# Sensors.net
KiCad netlist of a schematic drawn in Altium Designer
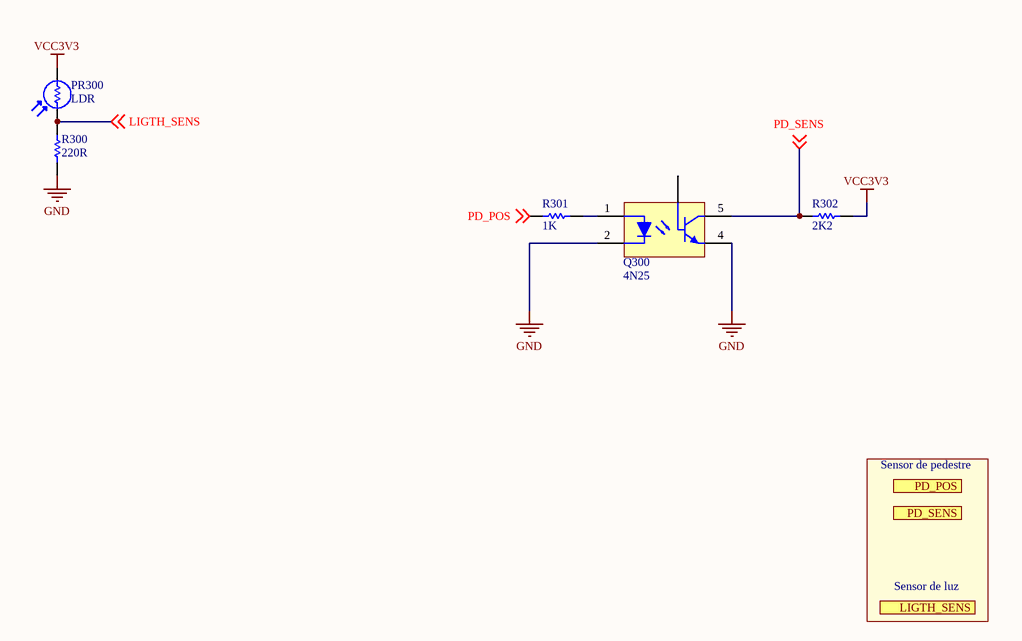
[diagram p0: Sensors.SchDoc]

(export (version "E")
  (design (tool "Eeschema 10.0.6"))
  (components
    (comp (ref "PR300")
      (value "LDR")
      (footprint "STL:LDR 3x0.5")
      (description "THROUGH HOLE PHOTORESISTORS ROHS")
      (fields
        (field (name "MANUFACTURER") "JCHL(Shenzhen Jing Chuang He Li Tech)")
        (field (name "MANUFACTURER PART NUMBER") "GL5506(4-7K)")
      )
      (libsource (lib "STL") (part "LDR GL5506(4-7K) SMD"))
    )
    (comp (ref "Q300")
      (value "4N25")
      (footprint "STL:6-SMD")
      (description "OPTOISO 4.17KV TRANS W/BASE 6SMD")
      (fields
        (field (name "MANUFACTURER") "ON Semiconductor")
        (field (name "MANUFACTURER PART NUMBER") "4N25SR2M")
      )
      (libsource (lib "STL") (part "OPTOISO 4N25S 2.5KV TRANS W/BASE 6SMD"))
    )
    (comp (ref "R300")
      (value "220R")
      (footprint "STL:CR2012-0805")
      (description "RES SMD 220 OHM 5% 1/8W 0805")
      (fields
        (field (name "MANUFACTURER") "Panasonic Electronic Components")
        (field (name "MANUFACTURER PART NUMBER") "ERJ-6GEYJ221V")
      )
      (libsource (lib "STL") (part "RES 220R OHM 5% 1/8W 0805 SMD"))
    )
    (comp (ref "R301")
      (value "1K")
      (footprint "STL:CR2012-0805")
      (description "RES SMD 1K OHM 1% 1/8W 0805")
      (fields
        (field (name "MANUFACTURER") "Yageo")
        (field (name "MANUFACTURER PART NUMBER") "RC0805FR-071KL")
      )
      (libsource (lib "STL") (part "RES 1K OHM 1% 1/8W 0805 SMD"))
    )
    (comp (ref "R302")
      (value "2K2")
      (footprint "STL:CR2012-0805")
      (description "RES SMD 2.2K OHM 5% 1/8W 0805")
      (fields
        (field (name "MANUFACTURER") "Panasonic Electronic Components")
        (field (name "PART#") "ERJ-6GEYJ222V")
      )
      (libsource (lib "STL") (part "RES 2K2 OHM 1/8W 5% 0805 SMD"))
    )
  )
  (nets
    (net (code "1") (name "GND") (class "Default")
      (node (ref "Q300") (pin "2") (pinfunction "K_2") (pintype "passive"))
      (node (ref "Q300") (pin "4") (pinfunction "E_4") (pintype "passive"))
      (node (ref "R300") (pin "1") (pinfunction "1_1") (pintype "passive"))
    )
    (net (code "2") (name "LIGTH_SENS") (class "Default")
      (node (ref "PR300") (pin "1") (pinfunction "1_1") (pintype "passive"))
      (node (ref "R300") (pin "2") (pinfunction "2_2") (pintype "passive"))
    )
    (net (code "3") (name "Net-(Q300-A)") (class "Default")
      (node (ref "Q300") (pin "1") (pinfunction "A_1") (pintype "passive"))
      (node (ref "R301") (pin "2") (pinfunction "2_2") (pintype "passive"))
    )
    (net (code "4") (name "PD_POS") (class "Default")
      (node (ref "R301") (pin "1") (pinfunction "1_1") (pintype "passive"))
    )
    (net (code "5") (name "PD_SENS") (class "Default")
      (node (ref "Q300") (pin "5") (pinfunction "C_5") (pintype "passive"))
      (node (ref "R302") (pin "1") (pinfunction "1_1") (pintype "passive"))
    )
    (net (code "6") (name "VCC3V3") (class "Default")
      (node (ref "PR300") (pin "2") (pinfunction "2_2") (pintype "passive"))
      (node (ref "R302") (pin "2") (pinfunction "2_2") (pintype "passive"))
    )
    (net (code "7") (name "unconnected-(Q300-B-Pad6)") (class "Default")
      (node (ref "Q300") (pin "6") (pinfunction "B_6") (pintype "passive"))
    )
  )
)
